# Sheet1.net
KiCad netlist of a schematic drawn in Altium Designer
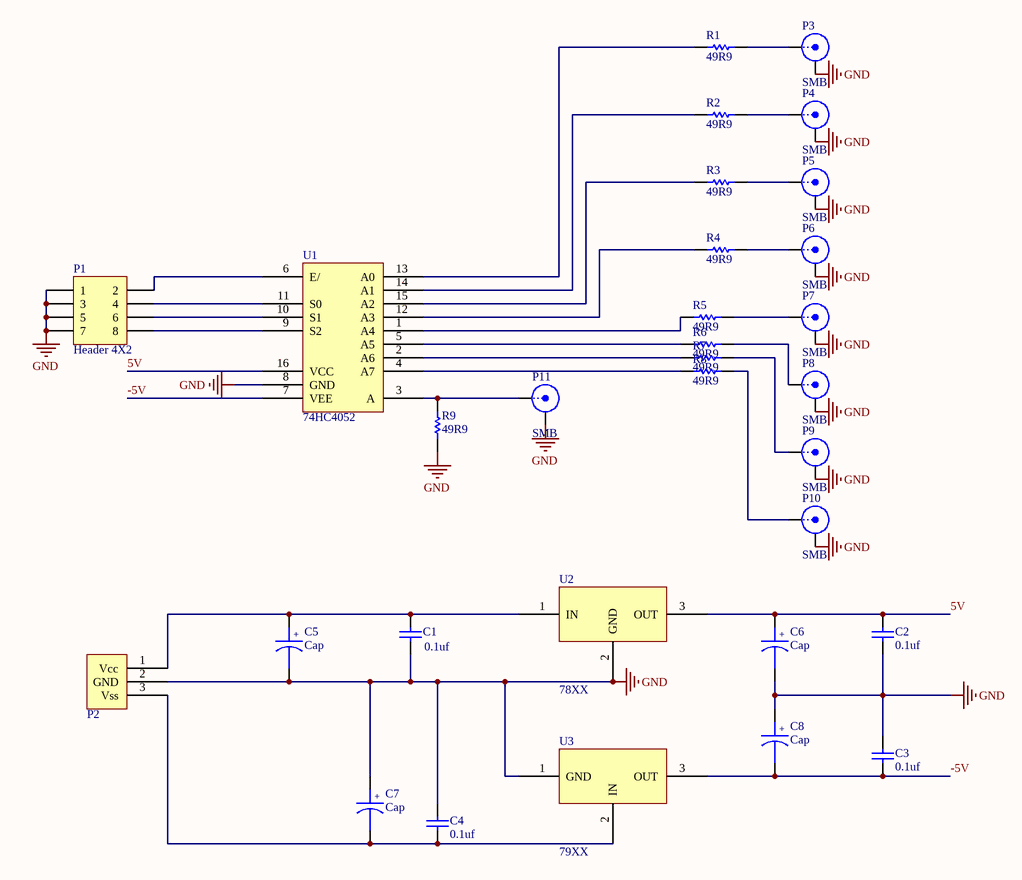
[diagram p0: Sheet1.SchDoc]

(export (version "E")
  (design (tool "Eeschema 10.0.6"))
  (components
    (comp (ref "C1") (value "0.1uf") (footprint "0805") (libsource (lib "Schlib1") (part "Cap")))
    (comp (ref "C2") (value "0.1uf") (footprint "0805") (libsource (lib "Schlib1") (part "Cap")))
    (comp (ref "C3") (value "0.1uf") (footprint "0805") (libsource (lib "Schlib1") (part "Cap")))
    (comp (ref "C4") (value "0.1uf") (footprint "0805") (libsource (lib "Schlib1") (part "Cap")))
    (comp (ref "C5")
      (value "Cap")
      (footprint "3216C-TYPE_A")
      (libsource (lib "Schlib1") (part "Tantalium Cap"))
    )
    (comp (ref "C6")
      (value "Cap")
      (footprint "3216C-TYPE_A")
      (libsource (lib "Schlib1") (part "Tantalium Cap"))
    )
    (comp (ref "C7")
      (value "Cap")
      (footprint "3216C-TYPE_A")
      (libsource (lib "Schlib1") (part "Tantalium Cap"))
    )
    (comp (ref "C8")
      (value "Cap")
      (footprint "3216C-TYPE_A")
      (libsource (lib "Schlib1") (part "Tantalium Cap"))
    )
    (comp (ref "P1")
      (value "Header 4X2")
      (footprint "HDR2X4")
      (description "Header, 4-Pin, Dual row")
      (fields (field (name "PUBLISHER") "Altium Limited"))
      (libsource (lib "Miscellaneous Connectors") (part "Header 4X2"))
    )
    (comp (ref "P2")
      (value "XH2.54-3p")
      (footprint "XH2.54-3p")
      (libsource (lib "Schlib1") (part "XH2.54-3p"))
    )
    (comp (ref "P3")
      (value "SMB")
      (footprint "SMB_V-RJ45")
      (description "SMB Straight Connector")
      (fields (field (name "PUBLISHER") "Altium Limited"))
      (libsource (lib "Miscellaneous Connectors") (part "SMB"))
    )
    (comp (ref "P4")
      (value "SMB")
      (footprint "SMB_V-RJ45")
      (description "SMB Straight Connector")
      (fields (field (name "PUBLISHER") "Altium Limited"))
      (libsource (lib "Miscellaneous Connectors") (part "SMB"))
    )
    (comp (ref "P5")
      (value "SMB")
      (footprint "SMB_V-RJ45")
      (description "SMB Straight Connector")
      (fields (field (name "PUBLISHER") "Altium Limited"))
      (libsource (lib "Miscellaneous Connectors") (part "SMB"))
    )
    (comp (ref "P6")
      (value "SMB")
      (footprint "SMB_V-RJ45")
      (description "SMB Straight Connector")
      (fields (field (name "PUBLISHER") "Altium Limited"))
      (libsource (lib "Miscellaneous Connectors") (part "SMB"))
    )
    (comp (ref "P7")
      (value "SMB")
      (footprint "SMB_V-RJ45")
      (description "SMB Straight Connector")
      (fields (field (name "PUBLISHER") "Altium Limited"))
      (libsource (lib "Miscellaneous Connectors") (part "SMB"))
    )
    (comp (ref "P8")
      (value "SMB")
      (footprint "SMB_V-RJ45")
      (description "SMB Straight Connector")
      (fields (field (name "PUBLISHER") "Altium Limited"))
      (libsource (lib "Miscellaneous Connectors") (part "SMB"))
    )
    (comp (ref "P9")
      (value "SMB")
      (footprint "SMB_V-RJ45")
      (description "SMB Straight Connector")
      (fields (field (name "PUBLISHER") "Altium Limited"))
      (libsource (lib "Miscellaneous Connectors") (part "SMB"))
    )
    (comp (ref "P10")
      (value "SMB")
      (footprint "SMB_V-RJ45")
      (description "SMB Straight Connector")
      (fields (field (name "PUBLISHER") "Altium Limited"))
      (libsource (lib "Miscellaneous Connectors") (part "SMB"))
    )
    (comp (ref "P11")
      (value "SMB")
      (footprint "SMB_V-RJ45")
      (description "SMB Straight Connector")
      (fields (field (name "PUBLISHER") "Altium Limited"))
      (libsource (lib "Miscellaneous Connectors") (part "SMB"))
    )
    (comp (ref "R1") (value "49R9") (footprint "0805") (libsource (lib "Schlib1") (part "Res")))
    (comp (ref "R2") (value "49R9") (footprint "0805") (libsource (lib "Schlib1") (part "Res")))
    (comp (ref "R3") (value "49R9") (footprint "0805") (libsource (lib "Schlib1") (part "Res")))
    (comp (ref "R4") (value "49R9") (footprint "0805") (libsource (lib "Schlib1") (part "Res")))
    (comp (ref "R5") (value "49R9") (footprint "0805") (libsource (lib "Schlib1") (part "Res")))
    (comp (ref "R6") (value "49R9") (footprint "0805") (libsource (lib "Schlib1") (part "Res")))
    (comp (ref "R7") (value "49R9") (footprint "0805") (libsource (lib "Schlib1") (part "Res")))
    (comp (ref "R8") (value "49R9") (footprint "0805") (libsource (lib "Schlib1") (part "Res")))
    (comp (ref "R9") (value "49R9") (footprint "0805") (libsource (lib "Schlib1") (part "Res")))
    (comp (ref "U1") (value "74HC4052") (footprint "TI-D16_L") (libsource (lib "Schlib1") (part "74HC4052")))
    (comp (ref "U2") (value "78XX") (footprint "TO-220") (libsource (lib "Schlib1") (part "78XX")))
    (comp (ref "U3") (value "79XX") (footprint "TO-220") (libsource (lib "Schlib1") (part "79XX")))
  )
  (nets
    (net (code "1") (name "/-5V") (class "Default")
      (node (ref "C3") (pin "2") (pinfunction "2_2") (pintype "passive"))
      (node (ref "C8") (pin "2") (pinfunction "2_2") (pintype "passive"))
      (node (ref "U1") (pin "7") (pinfunction "VEE_7") (pintype "passive"))
      (node (ref "U3") (pin "3") (pinfunction "OUT_3") (pintype "passive"))
    )
    (net (code "2") (name "/5V") (class "Default")
      (node (ref "C2") (pin "2") (pinfunction "2_2") (pintype "passive"))
      (node (ref "C6") (pin "1") (pinfunction "1_1") (pintype "passive"))
      (node (ref "U1") (pin "16") (pinfunction "VCC_16") (pintype "passive"))
      (node (ref "U2") (pin "3") (pinfunction "OUT_3") (pintype "passive"))
    )
    (net (code "3") (name "GND") (class "Default")
      (node (ref "C1") (pin "1") (pinfunction "1_1") (pintype "passive"))
      (node (ref "C2") (pin "1") (pinfunction "1_1") (pintype "passive"))
      (node (ref "C3") (pin "1") (pinfunction "1_1") (pintype "passive"))
      (node (ref "C4") (pin "2") (pinfunction "2_2") (pintype "passive"))
      (node (ref "C5") (pin "2") (pinfunction "2_2") (pintype "passive"))
      (node (ref "C6") (pin "2") (pinfunction "2_2") (pintype "passive"))
      (node (ref "C7") (pin "1") (pinfunction "1_1") (pintype "passive"))
      (node (ref "C8") (pin "1") (pinfunction "1_1") (pintype "passive"))
      (node (ref "P1") (pin "1") (pinfunction "1_1") (pintype "passive"))
      (node (ref "P1") (pin "3") (pinfunction "3_3") (pintype "passive"))
      (node (ref "P1") (pin "5") (pinfunction "5_5") (pintype "passive"))
      (node (ref "P1") (pin "7") (pinfunction "7_7") (pintype "passive"))
      (node (ref "P10") (pin "2") (pinfunction "Y_2") (pintype "passive"))
      (node (ref "P11") (pin "2") (pinfunction "Y_2") (pintype "passive"))
      (node (ref "P2") (pin "2") (pinfunction "GND_2") (pintype "passive"))
      (node (ref "P3") (pin "2") (pinfunction "Y_2") (pintype "passive"))
      (node (ref "P4") (pin "2") (pinfunction "Y_2") (pintype "passive"))
      (node (ref "P5") (pin "2") (pinfunction "Y_2") (pintype "passive"))
      (node (ref "P6") (pin "2") (pinfunction "Y_2") (pintype "passive"))
      (node (ref "P7") (pin "2") (pinfunction "Y_2") (pintype "passive"))
      (node (ref "P8") (pin "2") (pinfunction "Y_2") (pintype "passive"))
      (node (ref "P9") (pin "2") (pinfunction "Y_2") (pintype "passive"))
      (node (ref "R9") (pin "1") (pinfunction "1_1") (pintype "passive"))
      (node (ref "U1") (pin "8") (pinfunction "GND_8") (pintype "passive"))
      (node (ref "U2") (pin "2") (pinfunction "GND_2") (pintype "passive"))
      (node (ref "U3") (pin "1") (pinfunction "GND_1") (pintype "passive"))
    )
    (net (code "4") (name "Net-(P2-Vcc)") (class "Default")
      (node (ref "C1") (pin "2") (pinfunction "2_2") (pintype "passive"))
      (node (ref "C5") (pin "1") (pinfunction "1_1") (pintype "passive"))
      (node (ref "P2") (pin "1") (pinfunction "Vcc_1") (pintype "passive"))
      (node (ref "U2") (pin "1") (pinfunction "IN_1") (pintype "passive"))
    )
    (net (code "5") (name "Net-(P2-Vss)") (class "Default")
      (node (ref "C4") (pin "1") (pinfunction "1_1") (pintype "passive"))
      (node (ref "C7") (pin "2") (pinfunction "2_2") (pintype "passive"))
      (node (ref "P2") (pin "3") (pinfunction "Vss_3") (pintype "passive"))
      (node (ref "U3") (pin "2") (pinfunction "IN_2") (pintype "passive"))
    )
    (net (code "6") (name "Net-(P3-X)") (class "Default")
      (node (ref "P3") (pin "1") (pinfunction "X_1") (pintype "passive"))
      (node (ref "R1") (pin "2") (pinfunction "2_2") (pintype "passive"))
    )
    (net (code "7") (name "Net-(P4-X)") (class "Default")
      (node (ref "P4") (pin "1") (pinfunction "X_1") (pintype "passive"))
      (node (ref "R2") (pin "2") (pinfunction "2_2") (pintype "passive"))
    )
    (net (code "8") (name "Net-(P5-X)") (class "Default")
      (node (ref "P5") (pin "1") (pinfunction "X_1") (pintype "passive"))
      (node (ref "R3") (pin "2") (pinfunction "2_2") (pintype "passive"))
    )
    (net (code "9") (name "Net-(P6-X)") (class "Default")
      (node (ref "P6") (pin "1") (pinfunction "X_1") (pintype "passive"))
      (node (ref "R4") (pin "2") (pinfunction "2_2") (pintype "passive"))
    )
    (net (code "10") (name "Net-(P7-X)") (class "Default")
      (node (ref "P7") (pin "1") (pinfunction "X_1") (pintype "passive"))
      (node (ref "R5") (pin "2") (pinfunction "2_2") (pintype "passive"))
    )
    (net (code "11") (name "Net-(P8-X)") (class "Default")
      (node (ref "P8") (pin "1") (pinfunction "X_1") (pintype "passive"))
      (node (ref "R6") (pin "2") (pinfunction "2_2") (pintype "passive"))
    )
    (net (code "12") (name "Net-(P9-X)") (class "Default")
      (node (ref "P9") (pin "1") (pinfunction "X_1") (pintype "passive"))
      (node (ref "R7") (pin "2") (pinfunction "2_2") (pintype "passive"))
    )
    (net (code "13") (name "Net-(P10-X)") (class "Default")
      (node (ref "P10") (pin "1") (pinfunction "X_1") (pintype "passive"))
      (node (ref "R8") (pin "2") (pinfunction "2_2") (pintype "passive"))
    )
    (net (code "14") (name "Net-(P11-X)") (class "Default")
      (node (ref "P11") (pin "1") (pinfunction "X_1") (pintype "passive"))
      (node (ref "R9") (pin "2") (pinfunction "2_2") (pintype "passive"))
      (node (ref "U1") (pin "3") (pinfunction "A_3") (pintype "passive"))
    )
    (net (code "15") (name "Net-(U1-A0)") (class "Default")
      (node (ref "R1") (pin "1") (pinfunction "1_1") (pintype "passive"))
      (node (ref "U1") (pin "13") (pinfunction "A0_13") (pintype "passive"))
    )
    (net (code "16") (name "Net-(U1-A1)") (class "Default")
      (node (ref "R2") (pin "1") (pinfunction "1_1") (pintype "passive"))
      (node (ref "U1") (pin "14") (pinfunction "A1_14") (pintype "passive"))
    )
    (net (code "17") (name "Net-(U1-A2)") (class "Default")
      (node (ref "R3") (pin "1") (pinfunction "1_1") (pintype "passive"))
      (node (ref "U1") (pin "15") (pinfunction "A2_15") (pintype "passive"))
    )
    (net (code "18") (name "Net-(U1-A3)") (class "Default")
      (node (ref "R4") (pin "1") (pinfunction "1_1") (pintype "passive"))
      (node (ref "U1") (pin "12") (pinfunction "A3_12") (pintype "passive"))
    )
    (net (code "19") (name "Net-(U1-A4)") (class "Default")
      (node (ref "R5") (pin "1") (pinfunction "1_1") (pintype "passive"))
      (node (ref "U1") (pin "1") (pinfunction "A4_1") (pintype "passive"))
    )
    (net (code "20") (name "Net-(U1-A5)") (class "Default")
      (node (ref "R6") (pin "1") (pinfunction "1_1") (pintype "passive"))
      (node (ref "U1") (pin "5") (pinfunction "A5_5") (pintype "passive"))
    )
    (net (code "21") (name "Net-(U1-A6)") (class "Default")
      (node (ref "R7") (pin "1") (pinfunction "1_1") (pintype "passive"))
      (node (ref "U1") (pin "2") (pinfunction "A6_2") (pintype "passive"))
    )
    (net (code "22") (name "Net-(U1-A7)") (class "Default")
      (node (ref "R8") (pin "1") (pinfunction "1_1") (pintype "passive"))
      (node (ref "U1") (pin "4") (pinfunction "A7_4") (pintype "passive"))
    )
    (net (code "23") (name "Net-(U1-E{slash})") (class "Default")
      (node (ref "P1") (pin "2") (pinfunction "2_2") (pintype "passive"))
      (node (ref "U1") (pin "6") (pinfunction "E/_6") (pintype "passive"))
    )
    (net (code "24") (name "Net-(U1-S0)") (class "Default")
      (node (ref "P1") (pin "4") (pinfunction "4_4") (pintype "passive"))
      (node (ref "U1") (pin "11") (pinfunction "S0_11") (pintype "passive"))
    )
    (net (code "25") (name "Net-(U1-S1)") (class "Default")
      (node (ref "P1") (pin "6") (pinfunction "6_6") (pintype "passive"))
      (node (ref "U1") (pin "10") (pinfunction "S1_10") (pintype "passive"))
    )
    (net (code "26") (name "Net-(U1-S2)") (class "Default")
      (node (ref "P1") (pin "8") (pinfunction "8_8") (pintype "passive"))
      (node (ref "U1") (pin "9") (pinfunction "S2_9") (pintype "passive"))
    )
  )
)
